# reflow.net
KiCad netlist of a schematic drawn in EAGLE
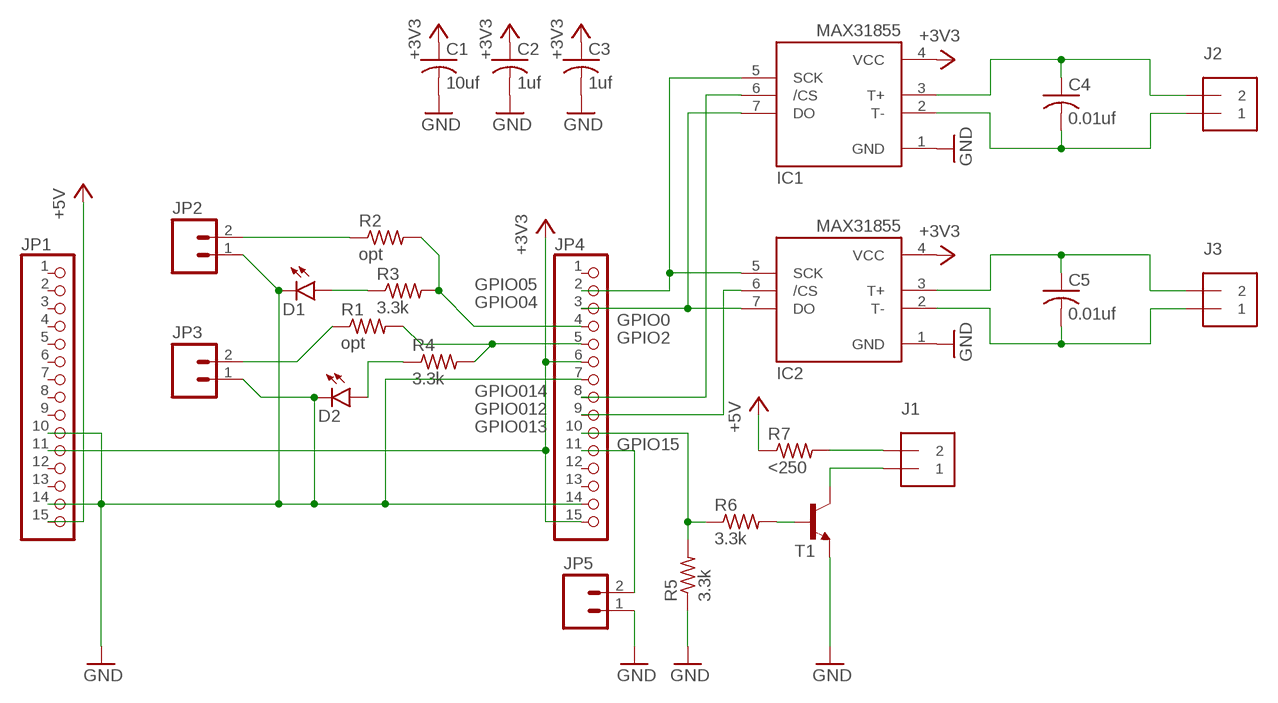
[diagram p0: schematic, sheet 1]

(export (version "E")
  (design (tool "Eeschema 10.0.6"))
  (components
    (comp (ref "C1")
      (value "10uf")
      (footprint "eagle-import:C0603")
      (libsource (lib "eagle-import") (part "C-USC0603"))
    )
    (comp (ref "C2")
      (value "1uf")
      (footprint "eagle-import:C0603")
      (libsource (lib "eagle-import") (part "C-USC0603"))
    )
    (comp (ref "C3")
      (value "1uf")
      (footprint "eagle-import:C0603")
      (libsource (lib "eagle-import") (part "C-USC0603"))
    )
    (comp (ref "C4")
      (value "0.01uf")
      (footprint "eagle-import:C0603")
      (libsource (lib "eagle-import") (part "C-USC0603"))
    )
    (comp (ref "C5")
      (value "0.01uf")
      (footprint "eagle-import:C0603")
      (libsource (lib "eagle-import") (part "C-USC0603"))
    )
    (comp (ref "D1")
      (value "LED0603")
      (footprint "eagle-import:LED-0603")
      (libsource (lib "eagle-import") (part "LED0603"))
    )
    (comp (ref "D2")
      (value "LED0603")
      (footprint "eagle-import:LED-0603")
      (libsource (lib "eagle-import") (part "LED0603"))
    )
    (comp (ref "IC1")
      (value "MAX31855")
      (footprint "eagle-import:SO08")
      (libsource (lib "eagle-import") (part "MAX6675"))
    )
    (comp (ref "IC2")
      (value "MAX31855")
      (footprint "eagle-import:SO08")
      (libsource (lib "eagle-import") (part "MAX6675"))
    )
    (comp (ref "J1")
      (value "1X2-3.5MM")
      (footprint "eagle-import:1X2-3.5MM")
      (libsource (lib "eagle-import") (part "1X2-3.5MM"))
    )
    (comp (ref "J2")
      (value "1X2-3.5MM")
      (footprint "eagle-import:1X2-3.5MM")
      (libsource (lib "eagle-import") (part "1X2-3.5MM"))
    )
    (comp (ref "J3")
      (value "1X2-3.5MM")
      (footprint "eagle-import:1X2-3.5MM")
      (libsource (lib "eagle-import") (part "1X2-3.5MM"))
    )
    (comp (ref "JP1")
      (value "PINHD-1X15")
      (footprint "eagle-import:1X15")
      (libsource (lib "eagle-import") (part "PINHD-1X15"))
    )
    (comp (ref "JP2")
      (value "M02PTH")
      (footprint "eagle-import:1X02")
      (libsource (lib "eagle-import") (part "M02PTH"))
    )
    (comp (ref "JP3")
      (value "M02PTH")
      (footprint "eagle-import:1X02")
      (libsource (lib "eagle-import") (part "M02PTH"))
    )
    (comp (ref "JP4")
      (value "PINHD-1X15")
      (footprint "eagle-import:1X15")
      (libsource (lib "eagle-import") (part "PINHD-1X15"))
    )
    (comp (ref "JP5")
      (value "M02PTH")
      (footprint "eagle-import:1X02")
      (libsource (lib "eagle-import") (part "M02PTH"))
    )
    (comp (ref "R1")
      (value "opt")
      (footprint "eagle-import:R0603")
      (libsource (lib "eagle-import") (part "R-US_R0603"))
    )
    (comp (ref "R2")
      (value "opt")
      (footprint "eagle-import:R0603")
      (libsource (lib "eagle-import") (part "R-US_R0603"))
    )
    (comp (ref "R3")
      (value "3.3k")
      (footprint "eagle-import:R0603")
      (libsource (lib "eagle-import") (part "R-US_R0603"))
    )
    (comp (ref "R4")
      (value "3.3k")
      (footprint "eagle-import:R0603")
      (libsource (lib "eagle-import") (part "R-US_R0603"))
    )
    (comp (ref "R5")
      (value "3.3k")
      (footprint "eagle-import:R0603")
      (libsource (lib "eagle-import") (part "R-US_R0603"))
    )
    (comp (ref "R6")
      (value "3.3k")
      (footprint "eagle-import:R0603")
      (libsource (lib "eagle-import") (part "R-US_R0603"))
    )
    (comp (ref "R7")
      (value "<250")
      (footprint "eagle-import:R0603")
      (libsource (lib "eagle-import") (part "R-US_R0603"))
    )
    (comp (ref "T1")
      (value "MMBT3904LT1-NPN-SOT23-BEC")
      (footprint "eagle-import:SOT23-BEC")
      (fields (field (name "MPN") "MMBT2222A"))
      (libsource (lib "eagle-import") (part "-NPN-SOT23-BECMMBT3904LT1"))
    )
  )
  (nets
    (net (code "1") (name "+3V3") (class "Default")
      (node (ref "C1") (pin "1") (pinfunction "1_1") (pintype "passive"))
      (node (ref "C2") (pin "1") (pinfunction "1_1") (pintype "passive"))
      (node (ref "C3") (pin "1") (pinfunction "1_1") (pintype "passive"))
      (node (ref "IC1") (pin "4") (pinfunction "VCC_4") (pintype "power_in"))
      (node (ref "IC2") (pin "4") (pinfunction "VCC_4") (pintype "power_in"))
      (node (ref "JP1") (pin "11") (pinfunction "11_11") (pintype "passive"))
      (node (ref "JP4") (pin "15") (pinfunction "15_15") (pintype "passive"))
      (node (ref "JP4") (pin "6") (pinfunction "6_6") (pintype "passive"))
    )
    (net (code "2") (name "+5V") (class "Default")
      (node (ref "JP1") (pin "15") (pinfunction "15_15") (pintype "passive"))
      (node (ref "R7") (pin "1") (pinfunction "1_1") (pintype "passive"))
    )
    (net (code "3") (name "GND") (class "Default")
      (node (ref "C1") (pin "2") (pinfunction "2_2") (pintype "passive"))
      (node (ref "C2") (pin "2") (pinfunction "2_2") (pintype "passive"))
      (node (ref "C3") (pin "2") (pinfunction "2_2") (pintype "passive"))
      (node (ref "D1") (pin "C") (pinfunction "C_C") (pintype "passive"))
      (node (ref "D2") (pin "C") (pinfunction "C_C") (pintype "passive"))
      (node (ref "IC1") (pin "1") (pinfunction "GND_1") (pintype "power_in"))
      (node (ref "IC2") (pin "1") (pinfunction "GND_1") (pintype "power_in"))
      (node (ref "JP1") (pin "10") (pinfunction "10_10") (pintype "passive"))
      (node (ref "JP1") (pin "14") (pinfunction "14_14") (pintype "passive"))
      (node (ref "JP2") (pin "1") (pinfunction "1_1") (pintype "passive"))
      (node (ref "JP3") (pin "1") (pinfunction "1_1") (pintype "passive"))
      (node (ref "JP4") (pin "14") (pinfunction "14_14") (pintype "passive"))
      (node (ref "JP4") (pin "7") (pinfunction "7_7") (pintype "passive"))
      (node (ref "JP5") (pin "1") (pinfunction "1_1") (pintype "passive"))
      (node (ref "R5") (pin "1") (pinfunction "1_1") (pintype "passive"))
      (node (ref "T1") (pin "E") (pinfunction "E_E") (pintype "passive"))
    )
    (net (code "4") (name "Net-(D1-PadA)") (class "Default")
      (node (ref "D1") (pin "A") (pinfunction "A_A") (pintype "passive"))
      (node (ref "R3") (pin "1") (pinfunction "1_1") (pintype "passive"))
    )
    (net (code "5") (name "Net-(D2-PadA)") (class "Default")
      (node (ref "D2") (pin "A") (pinfunction "A_A") (pintype "passive"))
      (node (ref "R4") (pin "1") (pinfunction "1_1") (pintype "passive"))
    )
    (net (code "6") (name "Net-(IC1-DO)") (class "Default")
      (node (ref "IC1") (pin "7") (pinfunction "DO_7") (pintype "output"))
      (node (ref "IC2") (pin "7") (pinfunction "DO_7") (pintype "output"))
      (node (ref "JP4") (pin "3") (pinfunction "3_3") (pintype "passive"))
    )
    (net (code "7") (name "Net-(IC1-SCK)") (class "Default")
      (node (ref "IC1") (pin "5") (pinfunction "SCK_5") (pintype "input"))
      (node (ref "IC2") (pin "5") (pinfunction "SCK_5") (pintype "input"))
      (node (ref "JP4") (pin "2") (pinfunction "2_2") (pintype "passive"))
    )
    (net (code "8") (name "Net-(IC1-T+)") (class "Default")
      (node (ref "C4") (pin "1") (pinfunction "1_1") (pintype "passive"))
      (node (ref "IC1") (pin "3") (pinfunction "T+_3") (pintype "input"))
      (node (ref "J2") (pin "2") (pinfunction "2_2") (pintype "passive"))
    )
    (net (code "9") (name "Net-(IC1-T-)") (class "Default")
      (node (ref "C4") (pin "2") (pinfunction "2_2") (pintype "passive"))
      (node (ref "IC1") (pin "2") (pinfunction "T-_2") (pintype "input"))
      (node (ref "J2") (pin "1") (pinfunction "1_1") (pintype "passive"))
    )
    (net (code "10") (name "Net-(IC1-{slash}CS)") (class "Default")
      (node (ref "IC1") (pin "6") (pinfunction "/CS_6") (pintype "input"))
      (node (ref "JP4") (pin "8") (pinfunction "8_8") (pintype "passive"))
    )
    (net (code "11") (name "Net-(IC2-T+)") (class "Default")
      (node (ref "C5") (pin "1") (pinfunction "1_1") (pintype "passive"))
      (node (ref "IC2") (pin "3") (pinfunction "T+_3") (pintype "input"))
      (node (ref "J3") (pin "2") (pinfunction "2_2") (pintype "passive"))
    )
    (net (code "12") (name "Net-(IC2-T-)") (class "Default")
      (node (ref "C5") (pin "2") (pinfunction "2_2") (pintype "passive"))
      (node (ref "IC2") (pin "2") (pinfunction "T-_2") (pintype "input"))
      (node (ref "J3") (pin "1") (pinfunction "1_1") (pintype "passive"))
    )
    (net (code "13") (name "Net-(IC2-{slash}CS)") (class "Default")
      (node (ref "IC2") (pin "6") (pinfunction "/CS_6") (pintype "input"))
      (node (ref "JP4") (pin "9") (pinfunction "9_9") (pintype "passive"))
    )
    (net (code "14") (name "Net-(J1-Pad1)") (class "Default")
      (node (ref "J1") (pin "1") (pinfunction "1_1") (pintype "passive"))
      (node (ref "T1") (pin "C") (pinfunction "C_C") (pintype "passive"))
    )
    (net (code "15") (name "Net-(J1-Pad2)") (class "Default")
      (node (ref "J1") (pin "2") (pinfunction "2_2") (pintype "passive"))
      (node (ref "R7") (pin "2") (pinfunction "2_2") (pintype "passive"))
    )
    (net (code "16") (name "Net-(JP2-Pad2)") (class "Default")
      (node (ref "JP2") (pin "2") (pinfunction "2_2") (pintype "passive"))
      (node (ref "R2") (pin "1") (pinfunction "1_1") (pintype "passive"))
    )
    (net (code "17") (name "Net-(JP3-Pad2)") (class "Default")
      (node (ref "JP3") (pin "2") (pinfunction "2_2") (pintype "passive"))
      (node (ref "R1") (pin "1") (pinfunction "1_1") (pintype "passive"))
    )
    (net (code "18") (name "Net-(JP4-Pad4)") (class "Default")
      (node (ref "JP4") (pin "4") (pinfunction "4_4") (pintype "passive"))
      (node (ref "R2") (pin "2") (pinfunction "2_2") (pintype "passive"))
      (node (ref "R3") (pin "2") (pinfunction "2_2") (pintype "passive"))
    )
    (net (code "19") (name "Net-(JP4-Pad5)") (class "Default")
      (node (ref "JP4") (pin "5") (pinfunction "5_5") (pintype "passive"))
      (node (ref "R1") (pin "2") (pinfunction "2_2") (pintype "passive"))
      (node (ref "R4") (pin "2") (pinfunction "2_2") (pintype "passive"))
    )
    (net (code "20") (name "Net-(JP4-Pad10)") (class "Default")
      (node (ref "JP4") (pin "10") (pinfunction "10_10") (pintype "passive"))
      (node (ref "R5") (pin "2") (pinfunction "2_2") (pintype "passive"))
      (node (ref "R6") (pin "1") (pinfunction "1_1") (pintype "passive"))
    )
    (net (code "21") (name "Net-(JP4-Pad11)") (class "Default")
      (node (ref "JP4") (pin "11") (pinfunction "11_11") (pintype "passive"))
      (node (ref "JP5") (pin "2") (pinfunction "2_2") (pintype "passive"))
    )
    (net (code "22") (name "Net-(R6-Pad2)") (class "Default")
      (node (ref "R6") (pin "2") (pinfunction "2_2") (pintype "passive"))
      (node (ref "T1") (pin "B") (pinfunction "B_B") (pintype "passive"))
    )
    (net (code "23") (name "unconnected-(JP1-Pad1)") (class "Default")
      (node (ref "JP1") (pin "1") (pinfunction "1_1") (pintype "passive"))
    )
    (net (code "24") (name "unconnected-(JP1-Pad2)") (class "Default")
      (node (ref "JP1") (pin "2") (pinfunction "2_2") (pintype "passive"))
    )
    (net (code "25") (name "unconnected-(JP1-Pad3)") (class "Default")
      (node (ref "JP1") (pin "3") (pinfunction "3_3") (pintype "passive"))
    )
    (net (code "26") (name "unconnected-(JP1-Pad4)") (class "Default")
      (node (ref "JP1") (pin "4") (pinfunction "4_4") (pintype "passive"))
    )
    (net (code "27") (name "unconnected-(JP1-Pad5)") (class "Default")
      (node (ref "JP1") (pin "5") (pinfunction "5_5") (pintype "passive"))
    )
    (net (code "28") (name "unconnected-(JP1-Pad6)") (class "Default")
      (node (ref "JP1") (pin "6") (pinfunction "6_6") (pintype "passive"))
    )
    (net (code "29") (name "unconnected-(JP1-Pad7)") (class "Default")
      (node (ref "JP1") (pin "7") (pinfunction "7_7") (pintype "passive"))
    )
    (net (code "30") (name "unconnected-(JP1-Pad8)") (class "Default")
      (node (ref "JP1") (pin "8") (pinfunction "8_8") (pintype "passive"))
    )
    (net (code "31") (name "unconnected-(JP1-Pad9)") (class "Default")
      (node (ref "JP1") (pin "9") (pinfunction "9_9") (pintype "passive"))
    )
    (net (code "32") (name "unconnected-(JP1-Pad12)") (class "Default")
      (node (ref "JP1") (pin "12") (pinfunction "12_12") (pintype "passive"))
    )
    (net (code "33") (name "unconnected-(JP1-Pad13)") (class "Default")
      (node (ref "JP1") (pin "13") (pinfunction "13_13") (pintype "passive"))
    )
    (net (code "34") (name "unconnected-(JP4-Pad1)") (class "Default")
      (node (ref "JP4") (pin "1") (pinfunction "1_1") (pintype "passive"))
    )
    (net (code "35") (name "unconnected-(JP4-Pad12)") (class "Default")
      (node (ref "JP4") (pin "12") (pinfunction "12_12") (pintype "passive"))
    )
    (net (code "36") (name "unconnected-(JP4-Pad13)") (class "Default")
      (node (ref "JP4") (pin "13") (pinfunction "13_13") (pintype "passive"))
    )
  )
)
